# FET_Channel.net
KiCad netlist of a schematic drawn in Altium Designer
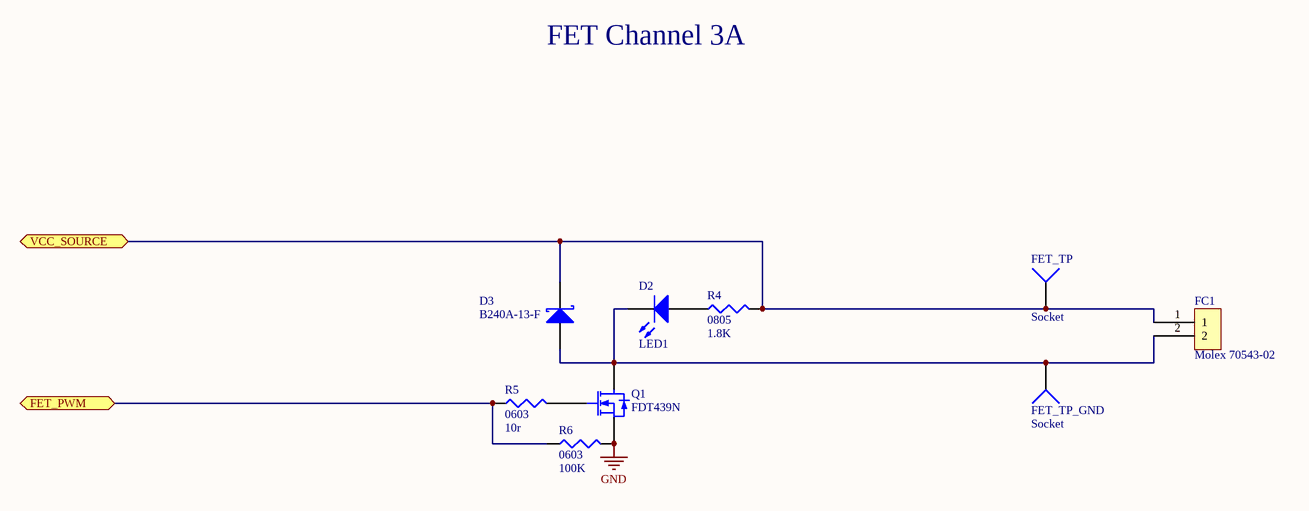
[diagram p0: FET Channel.SchDoc]

(export (version "E")
  (design (tool "Eeschema 10.0.6"))
  (components
    (comp (ref "D2")
      (value "LED1")
      (footprint "SM 0805 polarized")
      (description "Typical RED GaAs LED")
      (fields (field (name "PUBLISHER") "Altium Limited"))
      (libsource (lib "Miscellaneous Devices") (part "LED1"))
    )
    (comp (ref "D3")
      (value "B240A-13-F")
      (footprint "SMB")
      (description "Schottky Diode")
      (fields (field (name "PUBLISHER") "Altium Limited"))
      (libsource (lib "Miscellaneous Devices") (part "D Schottky"))
    )
    (comp (ref "FC1")
      (value "Molex 70543-02")
      (footprint "70543-02")
      (libsource (lib "ZMBo Schematic Library") (part "Molex 70543-02"))
    )
    (comp (ref "FET_TP")
      (value "Socket")
      (footprint "PIN1")
      (fields (field (name "PUBLISHER") "Altium Limited"))
      (libsource (lib "Miscellaneous Connectors") (part "Socket"))
    )
    (comp (ref "FET_TP_GND")
      (value "Socket")
      (footprint "PIN1")
      (fields (field (name "PUBLISHER") "Altium Limited"))
      (libsource (lib "Miscellaneous Connectors") (part "Socket"))
    )
    (comp (ref "Q1")
      (value "FDT439N")
      (footprint "Fairchild FDT439N")
      (description "N-Channel MOSFET")
      (fields (field (name "PUBLISHER") "Altium Limited"))
      (libsource (lib "ZMBo Schematic Library") (part "Fairchild FDT439N"))
    )
    (comp (ref "R4")
      (value "0805")
      (footprint "SM 0805 - gap trimmed")
      (description "Resistor")
      (fields (field (name "ALTIUM_VALUE") "1.8K") (field (name "PUBLISHER") "Altium Limited"))
      (libsource (lib "Miscellaneous Devices") (part "Res3"))
    )
    (comp (ref "R5")
      (value "0603")
      (footprint "J1-0603")
      (description "Resistor")
      (fields (field (name "ALTIUM_VALUE") "10r") (field (name "PUBLISHER") "Altium Limited"))
      (libsource (lib "Miscellaneous Devices") (part "Res3"))
    )
    (comp (ref "R6")
      (value "0603")
      (footprint "J1-0603")
      (description "Resistor")
      (fields (field (name "ALTIUM_VALUE") "100K") (field (name "PUBLISHER") "Altium Limited"))
      (libsource (lib "Miscellaneous Devices") (part "Res3"))
    )
  )
  (nets
    (net (code "1") (name "/FET_PWM") (class "Default")
      (node (ref "R5") (pin "1") (pinfunction "1_1") (pintype "passive"))
      (node (ref "R6") (pin "1") (pinfunction "1_1") (pintype "passive"))
    )
    (net (code "2") (name "/VCC_SOURCE") (class "Default")
      (node (ref "D3") (pin "2") (pinfunction "K_2") (pintype "passive"))
      (node (ref "FC1") (pin "1") (pinfunction "1_1") (pintype "passive"))
      (node (ref "FET_TP") (pin "1") (pinfunction "1_1") (pintype "passive"))
      (node (ref "R4") (pin "2") (pinfunction "2_2") (pintype "passive"))
    )
    (net (code "3") (name "2") (class "Default")
      (node (ref "Q1") (pin "4") (pinfunction "D_4") (pintype "passive"))
    )
    (net (code "4") (name "GND") (class "Default")
      (node (ref "Q1") (pin "3") (pinfunction "S_3") (pintype "passive"))
      (node (ref "R6") (pin "2") (pinfunction "2_2") (pintype "passive"))
    )
    (net (code "5") (name "Net-(D2-A)") (class "Default")
      (node (ref "D2") (pin "1") (pinfunction "A_1") (pintype "passive"))
      (node (ref "R4") (pin "1") (pinfunction "1_1") (pintype "passive"))
    )
    (net (code "6") (name "Net-(D2-K)") (class "Default")
      (node (ref "D2") (pin "2") (pinfunction "K_2") (pintype "passive"))
      (node (ref "D3") (pin "1") (pinfunction "A_1") (pintype "passive"))
      (node (ref "FC1") (pin "2") (pinfunction "2_2") (pintype "passive"))
      (node (ref "FET_TP_GND") (pin "1") (pinfunction "1_1") (pintype "passive"))
      (node (ref "Q1") (pin "2") (pinfunction "D_2") (pintype "passive"))
    )
    (net (code "7") (name "Net-(Q1-G)") (class "Default")
      (node (ref "Q1") (pin "1") (pinfunction "G_1") (pintype "passive"))
      (node (ref "R5") (pin "2") (pinfunction "2_2") (pintype "passive"))
    )
  )
)
